# SOIC8.net
KiCad netlist of a schematic drawn in Altium Designer
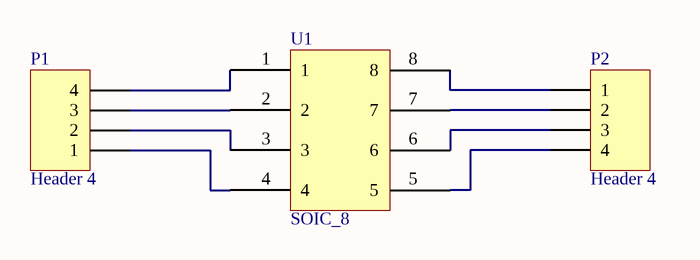
[diagram p0: SOIC8.SchDoc]

(export (version "E")
  (design (tool "Eeschema 10.0.6"))
  (components
    (comp (ref "P1")
      (value "Header 4")
      (footprint "HDR1X4")
      (description "Header, 4-Pin")
      (fields (field (name "PUBLISHER") "Altium Limited"))
      (libsource (lib "") (part "Header 4_1"))
    )
    (comp (ref "P2")
      (value "Header 4")
      (footprint "HDR1X4")
      (description "Header, 4-Pin")
      (fields (field (name "PUBLISHER") "Altium Limited"))
      (libsource (lib "Miscellaneous Connectors") (part "Header 4"))
    )
    (comp (ref "U1")
      (value "SOIC_8")
      (footprint "SOIC8")
      (libsource (lib "PCB_Breakout_Boards") (part "SOIC_8"))
    )
  )
  (nets
    (net (code "1") (name "Net-(P1-Pad1)") (class "Default")
      (node (ref "P1") (pin "1") (pinfunction "1_1") (pintype "passive"))
      (node (ref "U1") (pin "4") (pinfunction "4_4") (pintype "passive"))
    )
    (net (code "2") (name "Net-(P1-Pad2)") (class "Default")
      (node (ref "P1") (pin "2") (pinfunction "2_2") (pintype "passive"))
      (node (ref "U1") (pin "3") (pinfunction "3_3") (pintype "passive"))
    )
    (net (code "3") (name "Net-(P1-Pad3)") (class "Default")
      (node (ref "P1") (pin "3") (pinfunction "3_3") (pintype "passive"))
      (node (ref "U1") (pin "2") (pinfunction "2_2") (pintype "passive"))
    )
    (net (code "4") (name "Net-(P1-Pad4)") (class "Default")
      (node (ref "P1") (pin "4") (pinfunction "4_4") (pintype "passive"))
      (node (ref "U1") (pin "1") (pinfunction "1_1") (pintype "passive"))
    )
    (net (code "5") (name "Net-(P2-Pad1)") (class "Default")
      (node (ref "P2") (pin "1") (pinfunction "1_1") (pintype "passive"))
      (node (ref "U1") (pin "8") (pinfunction "8_8") (pintype "passive"))
    )
    (net (code "6") (name "Net-(P2-Pad2)") (class "Default")
      (node (ref "P2") (pin "2") (pinfunction "2_2") (pintype "passive"))
      (node (ref "U1") (pin "7") (pinfunction "7_7") (pintype "passive"))
    )
    (net (code "7") (name "Net-(P2-Pad3)") (class "Default")
      (node (ref "P2") (pin "3") (pinfunction "3_3") (pintype "passive"))
      (node (ref "U1") (pin "6") (pinfunction "6_6") (pintype "passive"))
    )
    (net (code "8") (name "Net-(P2-Pad4)") (class "Default")
      (node (ref "P2") (pin "4") (pinfunction "4_4") (pintype "passive"))
      (node (ref "U1") (pin "5") (pinfunction "5_5") (pintype "passive"))
    )
  )
)
